# BOOT_JTAG_AUX.net
KiCad netlist of a schematic drawn in Altium Designer
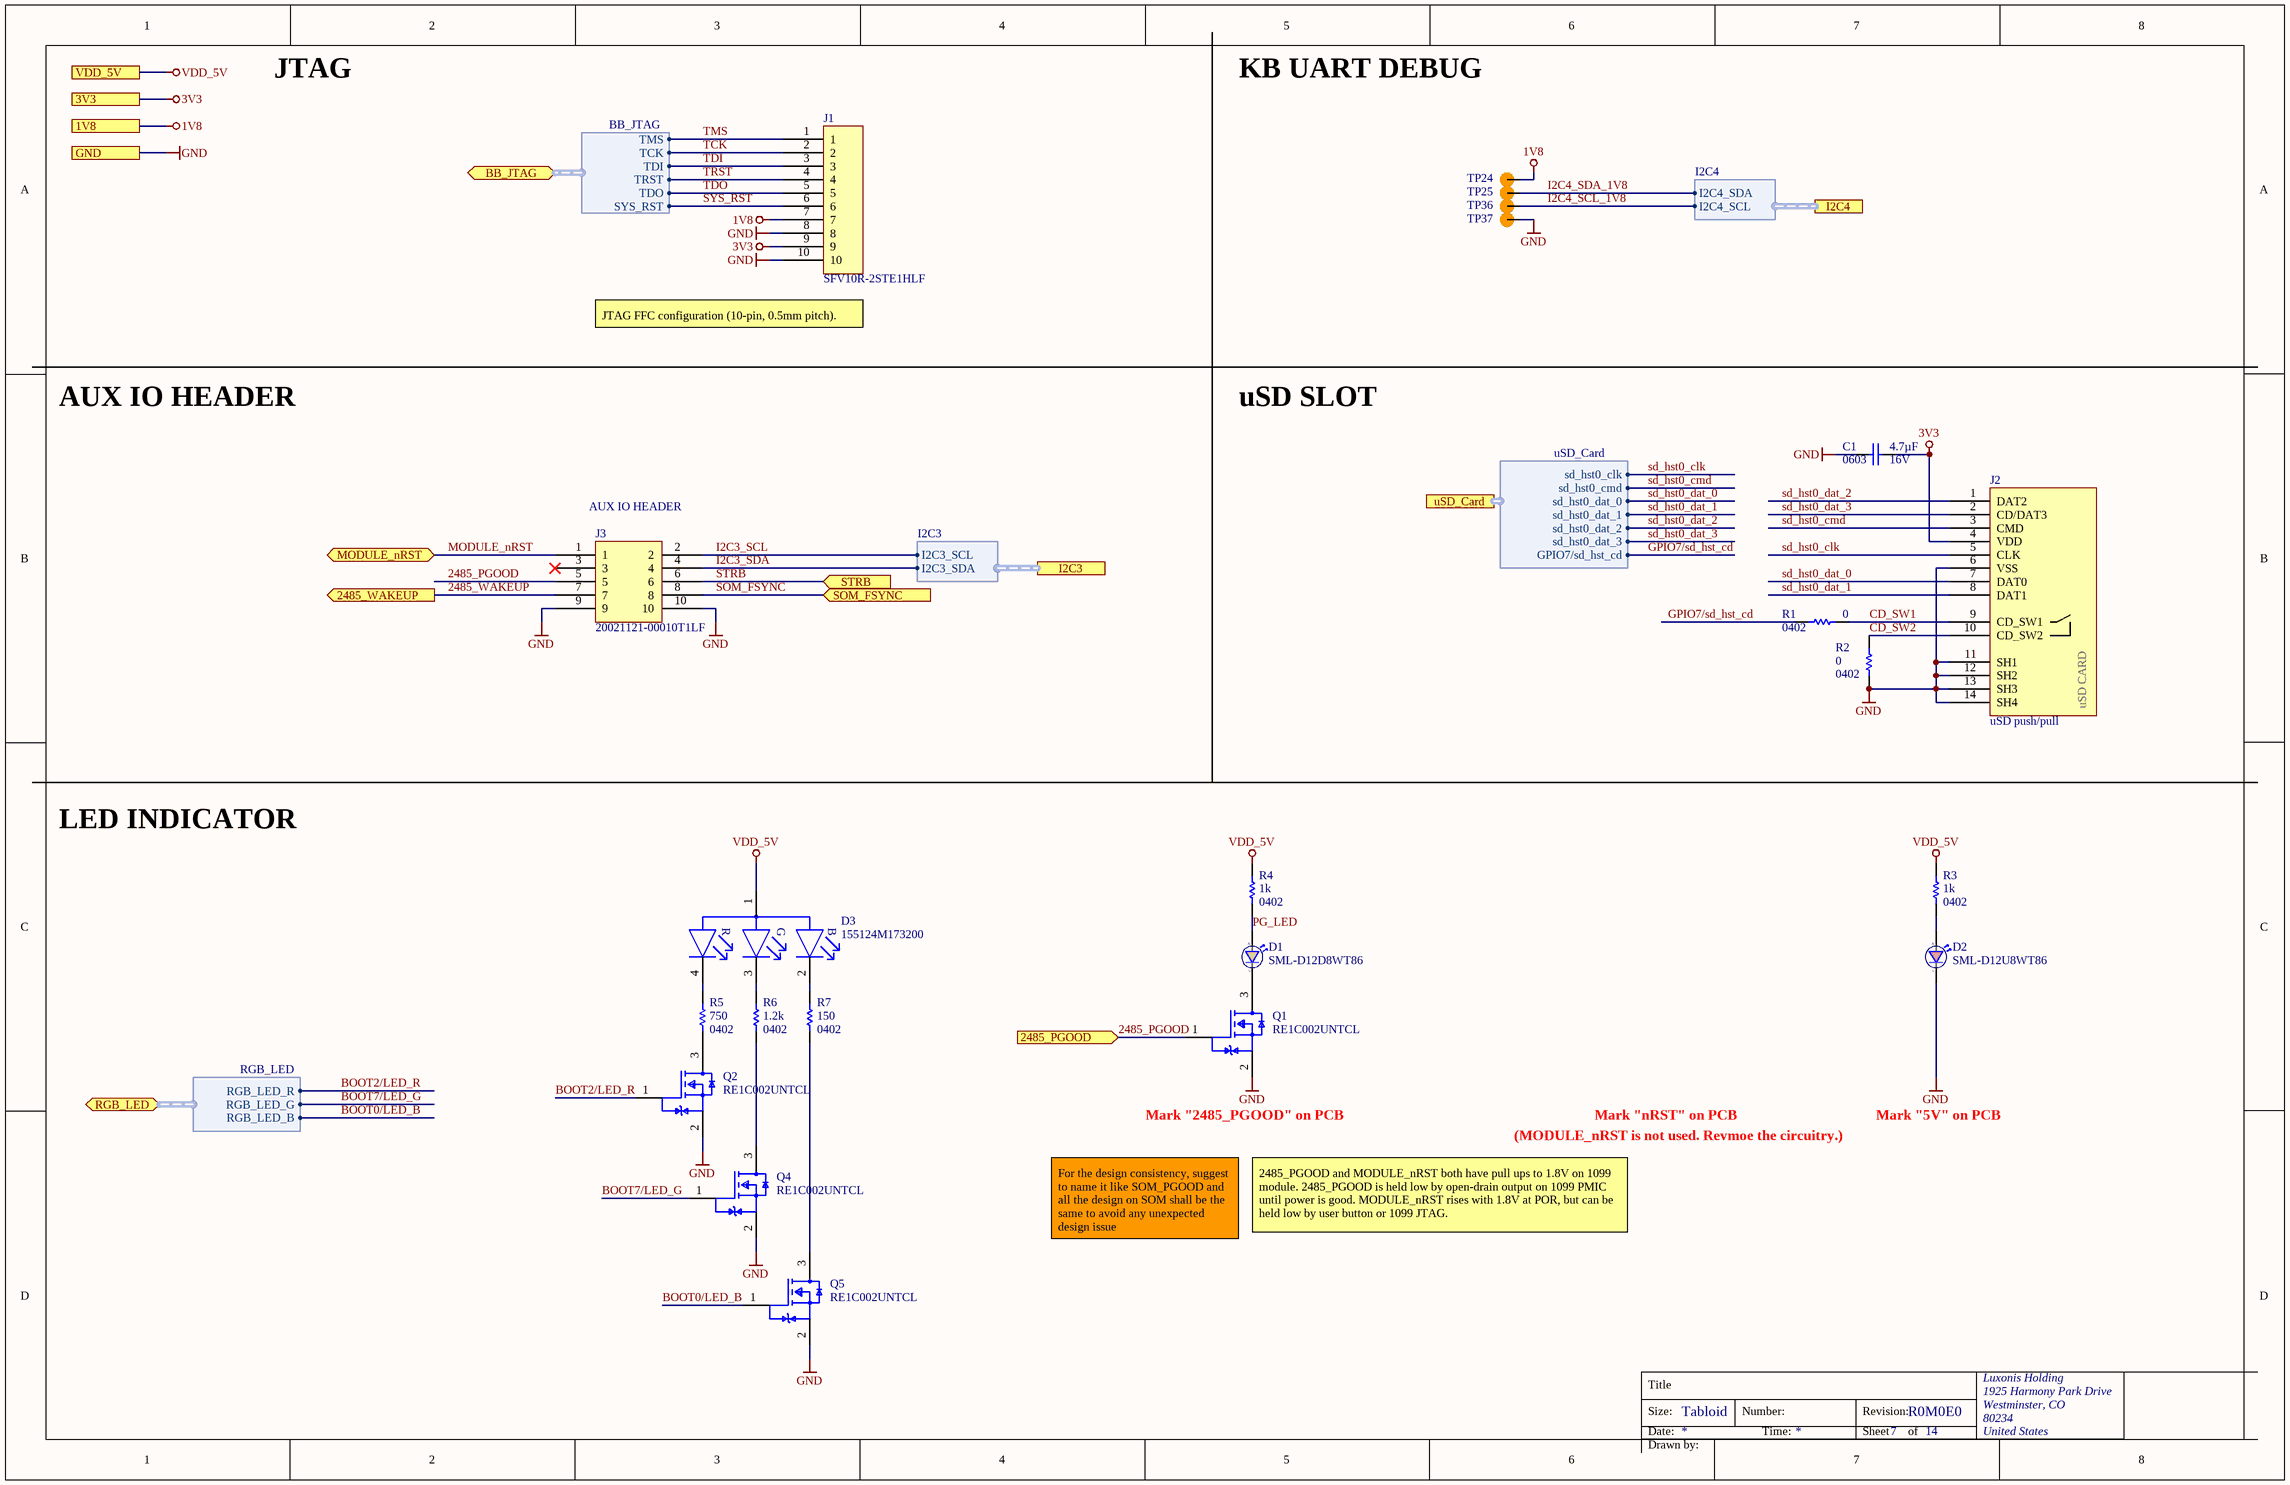
[diagram p0: BOOT_JTAG_AUX.SchDoc]

(export (version "E")
  (design (tool "Eeschema 10.0.6"))
  (components
    (comp (ref "C1")
      (value "4.7µF")
      (footprint "CAPC0603(1608)100_N")
      (description "CAP CER 4.7UF 16V X5R 0603 10%")
      (fields
        (field (name "VOLTAGE RATING") "16V")
        (field (name "CASE/PACKAGE") "0603")
        (field (name "TOLERANCE") "10%")
        (field (name "Comment") "GRM188R61C475KAAJD")
      )
      (libsource (lib "Luxonis LLC") (part "LLL153C70G474ME17E"))
    )
    (comp (ref "D1")
      (value "SML-D12D8WT86")
      (footprint "SML_D1xx8W")
      (description "LED ORANGE DIFFUSED 0603 SMD Orange 605nm LED Indication - Discrete 2.2V 0603 (1608 Metric)")
      (libsource (lib "Luxonis LLC") (part "SML-D12D8WT86"))
    )
    (comp (ref "D2")
      (value "SML-D12U8WT86")
      (footprint "SML_D1xx8W")
      (description "LED RED DIFFUSED 0603 SMD Red 620nm LED Indication - Discrete 2.2V 0603 (1608 Metric)")
      (libsource (lib "Luxonis LLC") (part "SML-D12U8WT86"))
    )
    (comp (ref "D3")
      (value "155124M173200")
      (footprint "FP-155124M173200-MFG")
      (description "Triple Color LED")
      (libsource (lib "Luxonis LLC") (part "8635049b720462866f33dfa80272b1c"))
    )
    (comp (ref "J1")
      (value "SFV10R-2STE1HLF")
      (footprint "SFV10R-2STE1HLF")
      (description "CONN FFC TOP 10POS 0.50MM R/A")
      (libsource (lib "Luxonis LLC") (part "SFV10R-2STE1HLF"))
    )
    (comp (ref "J2")
      (value "uSD push/pull")
      (footprint "LuxonisMaster:104031-0811")
      (description "CONN MICRO SD CARD PUSH-PULL R/A")
      (libsource (lib "LuxonisMaster") (part "104031-0811"))
    )
    (comp (ref "J3")
      (value "20021121-00010T1LF")
      (footprint "LuxonisMaster:20021121-00010T1LF")
      (description "CONN HEADER SMD 10POS 1.27MM")
      (libsource (lib "LuxonisMaster") (part "20021121-00010T1LF"))
    )
    (comp (ref "Q1")
      (value "RE1C002UNTCL")
      (footprint "RE1C002UNTCL")
      (description "MOSFET N-CH 20V 0.2A EMT3")
      (libsource (lib "Luxonis LLC") (part "RE1C002UNTCL"))
    )
    (comp (ref "Q2")
      (value "RE1C002UNTCL")
      (footprint "RE1C002UNTCL")
      (description "MOSFET N-CH 20V 0.2A EMT3")
      (libsource (lib "Luxonis LLC") (part "RE1C002UNTCL"))
    )
    (comp (ref "Q4")
      (value "RE1C002UNTCL")
      (footprint "RE1C002UNTCL")
      (description "MOSFET N-CH 20V 0.2A EMT3")
      (libsource (lib "Luxonis LLC") (part "RE1C002UNTCL"))
    )
    (comp (ref "Q5")
      (value "RE1C002UNTCL")
      (footprint "RE1C002UNTCL")
      (description "MOSFET N-CH 20V 0.2A EMT3")
      (libsource (lib "Luxonis LLC") (part "RE1C002UNTCL"))
    )
    (comp (ref "R1")
      (value "0")
      (footprint "RESC0402(1005)_L")
      (description "RES SMD 0 OHM 5% 1/16W 0402")
      (fields
        (field (name "CASE/PACKAGE") "0402")
        (field (name "TOLERANCE") "5%")
        (field (name "Comment") "CRCW04020000Z0ED")
      )
      (libsource (lib "Luxonis LLC") (part "Default resistor symbol"))
    )
    (comp (ref "R2")
      (value "0")
      (footprint "RESC0402(1005)_L")
      (description "RES SMD 0 OHM 5% 1/16W 0402")
      (fields
        (field (name "CASE/PACKAGE") "0402")
        (field (name "TOLERANCE") "5%")
        (field (name "Comment") "CRCW04020000Z0ED")
      )
      (libsource (lib "Luxonis LLC") (part "Default resistor symbol"))
    )
    (comp (ref "R3")
      (value "1k")
      (footprint "RESC0402(1005)_L")
      (description "RES SMD 1K OHM 1% 1/16W 0402")
      (fields
        (field (name "CASE/PACKAGE") "0402")
        (field (name "TOLERANCE") "1%")
        (field (name "Comment") "RC0402FR-071KL")
      )
      (libsource (lib "Luxonis LLC") (part "Default resistor symbol"))
    )
    (comp (ref "R4")
      (value "1k")
      (footprint "RESC0402(1005)_L")
      (description "RES SMD 1K OHM 1% 1/16W 0402")
      (fields
        (field (name "CASE/PACKAGE") "0402")
        (field (name "TOLERANCE") "1%")
        (field (name "Comment") "RC0402FR-071KL")
      )
      (libsource (lib "Luxonis LLC") (part "Default resistor symbol"))
    )
    (comp (ref "R5")
      (value "750")
      (footprint "RESC1005X40X25NL05T05")
      (description "RES SMD 750 OHM 1% 0.1W 0402")
      (fields
        (field (name "CASE/PACKAGE") "0402")
        (field (name "TOLERANCE") "1%")
        (field (name "Comment") "ERJ-2RKF7500X")
      )
      (libsource (lib "Luxonis LLC") (part "Default resistor symbol"))
    )
    (comp (ref "R6")
      (value "1.2k")
      (footprint "RESC1005X40X25NL05T05")
      (description "RES SMD 1.2K OHM 1% 0.063W 0402")
      (fields
        (field (name "CASE/PACKAGE") "0402")
        (field (name "TOLERANCE") "1%")
        (field (name "Comment") "CRCW04021K20FKED")
      )
      (libsource (lib "Luxonis LLC") (part "Default resistor symbol"))
    )
    (comp (ref "R7")
      (value "150")
      (footprint "RESC1005X40X25NL05T10")
      (description "RES SMD 150 OHM 1% 1/16W 0402")
      (fields
        (field (name "CASE/PACKAGE") "0402")
        (field (name "TOLERANCE") "1%")
        (field (name "Comment") "RC0402FR-07150RL")
      )
      (libsource (lib "Luxonis LLC") (part "Default resistor symbol"))
    )
    (comp (ref "TP24")
      (value "TEST_POINT")
      (footprint "TP075_150_NS")
      (libsource (lib "Luxonis LLC") (part "TEST_POINT"))
    )
    (comp (ref "TP25")
      (value "TEST_POINT")
      (footprint "TP075_150_NS")
      (libsource (lib "Luxonis LLC") (part "TEST_POINT"))
    )
    (comp (ref "TP36")
      (value "TEST_POINT")
      (footprint "TP075_150_NS")
      (libsource (lib "Luxonis LLC") (part "TEST_POINT"))
    )
    (comp (ref "TP37")
      (value "TEST_POINT")
      (footprint "TP075_150_NS")
      (libsource (lib "Luxonis LLC") (part "TEST_POINT"))
    )
  )
  (nets
    (net (code "6") (name "/2485_PGOOD") (class "Default")
      (node (ref "J3") (pin "5") (pinfunction "5_5") (pintype "passive"))
      (node (ref "Q1") (pin "1") (pinfunction "Gate_1") (pintype "passive"))
    )
    (net (code "7") (name "/2485_WAKEUP") (class "Default")
      (node (ref "J3") (pin "7") (pinfunction "7_7") (pintype "passive"))
    )
    (net (code "8") (name "/BOOT0{slash}LED_B") (class "Default")
      (node (ref "Q5") (pin "1") (pinfunction "Gate_1") (pintype "passive"))
    )
    (net (code "9") (name "/BOOT2{slash}LED_R") (class "Default")
      (node (ref "Q2") (pin "1") (pinfunction "Gate_1") (pintype "passive"))
    )
    (net (code "10") (name "/BOOT7{slash}LED_G") (class "Default")
      (node (ref "Q4") (pin "1") (pinfunction "Gate_1") (pintype "passive"))
    )
    (net (code "11") (name "/CD_SW1") (class "Default")
      (node (ref "J2") (pin "9") (pinfunction "CD_SW1_9") (pintype "passive"))
      (node (ref "R1") (pin "2") (pinfunction "2_2") (pintype "passive"))
    )
    (net (code "12") (name "/CD_SW2") (class "Default")
      (node (ref "J2") (pin "10") (pinfunction "CD_SW2_10") (pintype "passive"))
      (node (ref "R2") (pin "2") (pinfunction "2_2") (pintype "passive"))
    )
    (net (code "13") (name "/GPIO7{slash}sd_hst_cd") (class "Default")
      (node (ref "R1") (pin "1") (pinfunction "1_1") (pintype "passive"))
    )
    (net (code "14") (name "/I2C3_SCL") (class "Default")
      (node (ref "J3") (pin "2") (pinfunction "2_2") (pintype "passive"))
    )
    (net (code "15") (name "/I2C3_SDA") (class "Default")
      (node (ref "J3") (pin "4") (pinfunction "4_4") (pintype "passive"))
    )
    (net (code "16") (name "/I2C4_SCL_1V8") (class "Default")
      (node (ref "TP36") (pin "1") (pintype "passive"))
    )
    (net (code "17") (name "/I2C4_SDA_1V8") (class "Default")
      (node (ref "TP25") (pin "1") (pintype "passive"))
    )
    (net (code "18") (name "/MODULE_nRST") (class "Default")
      (node (ref "J3") (pin "1") (pinfunction "1_1") (pintype "passive"))
    )
    (net (code "19") (name "/PG_LED") (class "Default")
      (node (ref "D1") (pin "2") (pinfunction "A_2") (pintype "passive"))
      (node (ref "R4") (pin "1") (pinfunction "1_1") (pintype "passive"))
    )
    (net (code "20") (name "/SOM_FSYNC") (class "Default")
      (node (ref "J3") (pin "8") (pinfunction "8_8") (pintype "passive"))
    )
    (net (code "21") (name "/STRB") (class "Default")
      (node (ref "J3") (pin "6") (pinfunction "6_6") (pintype "passive"))
    )
    (net (code "22") (name "/SYS_RST") (class "Default")
      (node (ref "J1") (pin "6") (pinfunction "6_6") (pintype "passive"))
    )
    (net (code "23") (name "/TCK") (class "Default")
      (node (ref "J1") (pin "2") (pinfunction "2_2") (pintype "passive"))
    )
    (net (code "24") (name "/TDI") (class "Default")
      (node (ref "J1") (pin "3") (pinfunction "3_3") (pintype "passive"))
    )
    (net (code "25") (name "/TDO") (class "Default")
      (node (ref "J1") (pin "5") (pinfunction "5_5") (pintype "passive"))
    )
    (net (code "26") (name "/TMS") (class "Default")
      (node (ref "J1") (pin "1") (pinfunction "1_1") (pintype "passive"))
    )
    (net (code "27") (name "/TRST") (class "Default")
      (node (ref "J1") (pin "4") (pinfunction "4_4") (pintype "passive"))
    )
    (net (code "28") (name "/sd_hst0_clk") (class "Default")
      (node (ref "J2") (pin "5") (pinfunction "CLK_5") (pintype "passive"))
    )
    (net (code "29") (name "/sd_hst0_cmd") (class "Default")
      (node (ref "J2") (pin "3") (pinfunction "CMD_3") (pintype "passive"))
    )
    (net (code "30") (name "/sd_hst0_dat_0") (class "Default")
      (node (ref "J2") (pin "7") (pinfunction "DAT0_7") (pintype "passive"))
    )
    (net (code "31") (name "/sd_hst0_dat_1") (class "Default")
      (node (ref "J2") (pin "8") (pinfunction "DAT1_8") (pintype "passive"))
    )
    (net (code "32") (name "/sd_hst0_dat_2") (class "Default")
      (node (ref "J2") (pin "1") (pinfunction "DAT2_1") (pintype "passive"))
    )
    (net (code "33") (name "/sd_hst0_dat_3") (class "Default")
      (node (ref "J2") (pin "2") (pinfunction "CD/DAT3_2") (pintype "passive"))
    )
    (net (code "39") (name "1V8") (class "Default")
      (node (ref "J1") (pin "7") (pinfunction "7_7") (pintype "passive"))
      (node (ref "TP24") (pin "1") (pintype "passive"))
    )
    (net (code "40") (name "3V3") (class "Default")
      (node (ref "C1") (pin "1") (pinfunction "1_1") (pintype "passive"))
      (node (ref "J1") (pin "9") (pinfunction "9_9") (pintype "passive"))
      (node (ref "J2") (pin "4") (pinfunction "VDD_4") (pintype "passive"))
    )
    (net (code "41") (name "GND") (class "Default")
      (node (ref "C1") (pin "2") (pinfunction "2_2") (pintype "passive"))
      (node (ref "D2") (pin "1") (pinfunction "C_1") (pintype "passive"))
      (node (ref "J1") (pin "10") (pinfunction "10_10") (pintype "passive"))
      (node (ref "J1") (pin "8") (pinfunction "8_8") (pintype "passive"))
      (node (ref "J2") (pin "11") (pinfunction "SH1_11") (pintype "passive"))
      (node (ref "J2") (pin "12") (pinfunction "SH2_12") (pintype "passive"))
      (node (ref "J2") (pin "13") (pinfunction "SH3_13") (pintype "passive"))
      (node (ref "J2") (pin "14") (pinfunction "SH4_14") (pintype "passive"))
      (node (ref "J2") (pin "6") (pinfunction "VSS_6") (pintype "passive"))
      (node (ref "J3") (pin "10") (pinfunction "10_10") (pintype "passive"))
      (node (ref "J3") (pin "9") (pinfunction "9_9") (pintype "passive"))
      (node (ref "Q1") (pin "2") (pinfunction "Source_2") (pintype "passive"))
      (node (ref "Q2") (pin "2") (pinfunction "Source_2") (pintype "passive"))
      (node (ref "Q4") (pin "2") (pinfunction "Source_2") (pintype "passive"))
      (node (ref "Q5") (pin "2") (pinfunction "Source_2") (pintype "passive"))
      (node (ref "R2") (pin "1") (pinfunction "1_1") (pintype "passive"))
      (node (ref "TP37") (pin "1") (pintype "passive"))
    )
    (net (code "42") (name "Net-(D1-C)") (class "Default")
      (node (ref "D1") (pin "1") (pinfunction "C_1") (pintype "passive"))
      (node (ref "Q1") (pin "3") (pinfunction "Drain_3") (pintype "passive"))
    )
    (net (code "43") (name "Net-(D2-A)") (class "Default")
      (node (ref "D2") (pin "2") (pinfunction "A_2") (pintype "passive"))
      (node (ref "R3") (pin "1") (pinfunction "1_1") (pintype "passive"))
    )
    (net (code "44") (name "Net-(D3-BLUE_C)") (class "Default")
      (node (ref "D3") (pin "2") (pinfunction "BLUE_C_2") (pintype "passive"))
      (node (ref "R7") (pin "2") (pinfunction "2_2") (pintype "passive"))
    )
    (net (code "45") (name "Net-(D3-GREEN_C)") (class "Default")
      (node (ref "D3") (pin "3") (pinfunction "GREEN_C_3") (pintype "passive"))
      (node (ref "R6") (pin "2") (pinfunction "2_2") (pintype "passive"))
    )
    (net (code "46") (name "Net-(D3-RED_C)") (class "Default")
      (node (ref "D3") (pin "4") (pinfunction "RED_C_4") (pintype "passive"))
      (node (ref "R5") (pin "2") (pinfunction "2_2") (pintype "passive"))
    )
    (net (code "47") (name "Net-(Q2-Drain)") (class "Default")
      (node (ref "Q2") (pin "3") (pinfunction "Drain_3") (pintype "passive"))
      (node (ref "R5") (pin "1") (pinfunction "1_1") (pintype "passive"))
    )
    (net (code "48") (name "Net-(Q4-Drain)") (class "Default")
      (node (ref "Q4") (pin "3") (pinfunction "Drain_3") (pintype "passive"))
      (node (ref "R6") (pin "1") (pinfunction "1_1") (pintype "passive"))
    )
    (net (code "49") (name "Net-(Q5-Drain)") (class "Default")
      (node (ref "Q5") (pin "3") (pinfunction "Drain_3") (pintype "passive"))
      (node (ref "R7") (pin "1") (pinfunction "1_1") (pintype "passive"))
    )
    (net (code "50") (name "VDD_5V") (class "Default")
      (node (ref "D3") (pin "1") (pinfunction "COMMON_ANODE_1") (pintype "passive"))
      (node (ref "R3") (pin "2") (pinfunction "2_2") (pintype "passive"))
      (node (ref "R4") (pin "2") (pinfunction "2_2") (pintype "passive"))
    )
    (net (code "51") (name "unconnected-(J3-Pad3)") (class "Default")
      (node (ref "J3") (pin "3") (pinfunction "3_3") (pintype "passive+no_connect"))
    )
  )
)
